# SHDN-S05-V00-Connector.net
KiCad netlist of a schematic drawn in Altium Designer
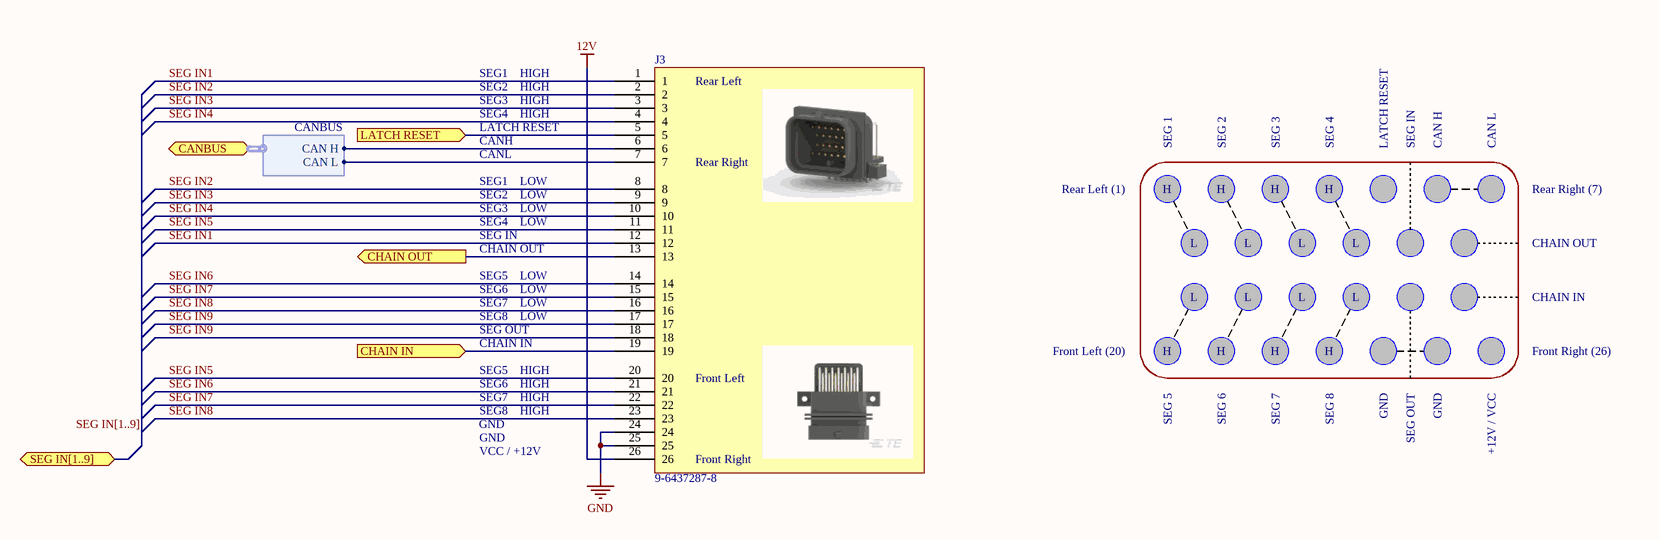
[diagram p0: SHDN-S05-V00-Connector.SchDoc]

(export (version "E")
  (design (tool "Eeschema 10.0.6"))
  (components
    (comp (ref "J3")
      (value "9-6437287-8")
      (footprint "SUPERSEAL RIGHT 26WAY")
      (description "Connector Header Through Hole, Right Angle 26 position 0.118\" (3.00mm)")
      (libsource (lib "QUTMS_SupersealPCB") (part "9-6437287-8"))
    )
  )
  (nets
    (net (code "2") (name "/CAN H") (class "Default")
      (node (ref "J3") (pin "6") (pinfunction "6_6") (pintype "passive"))
    )
    (net (code "3") (name "/CAN L") (class "Default")
      (node (ref "J3") (pin "7") (pinfunction "7_7") (pintype "passive"))
    )
    (net (code "4") (name "/CHAIN IN") (class "Default")
      (node (ref "J3") (pin "19") (pinfunction "19_19") (pintype "passive"))
    )
    (net (code "5") (name "/CHAIN OUT") (class "Default")
      (node (ref "J3") (pin "13") (pinfunction "13_13") (pintype "passive"))
    )
    (net (code "6") (name "/LATCH RESET") (class "Default")
      (node (ref "J3") (pin "5") (pinfunction "5_5") (pintype "passive"))
    )
    (net (code "7") (name "/SEG IN1") (class "Default")
      (node (ref "J3") (pin "1") (pinfunction "1_1") (pintype "passive"))
      (node (ref "J3") (pin "12") (pinfunction "12_12") (pintype "passive"))
    )
    (net (code "8") (name "/SEG IN2") (class "Default")
      (node (ref "J3") (pin "2") (pinfunction "2_2") (pintype "passive"))
      (node (ref "J3") (pin "8") (pinfunction "8_8") (pintype "passive"))
    )
    (net (code "9") (name "/SEG IN3") (class "Default")
      (node (ref "J3") (pin "3") (pinfunction "3_3") (pintype "passive"))
      (node (ref "J3") (pin "9") (pinfunction "9_9") (pintype "passive"))
    )
    (net (code "10") (name "/SEG IN4") (class "Default")
      (node (ref "J3") (pin "10") (pinfunction "10_10") (pintype "passive"))
      (node (ref "J3") (pin "4") (pinfunction "4_4") (pintype "passive"))
    )
    (net (code "11") (name "/SEG IN5") (class "Default")
      (node (ref "J3") (pin "11") (pinfunction "11_11") (pintype "passive"))
      (node (ref "J3") (pin "20") (pinfunction "20_20") (pintype "passive"))
    )
    (net (code "12") (name "/SEG IN6") (class "Default")
      (node (ref "J3") (pin "14") (pinfunction "14_14") (pintype "passive"))
      (node (ref "J3") (pin "21") (pinfunction "21_21") (pintype "passive"))
    )
    (net (code "13") (name "/SEG IN7") (class "Default")
      (node (ref "J3") (pin "15") (pinfunction "15_15") (pintype "passive"))
      (node (ref "J3") (pin "22") (pinfunction "22_22") (pintype "passive"))
    )
    (net (code "14") (name "/SEG IN8") (class "Default")
      (node (ref "J3") (pin "16") (pinfunction "16_16") (pintype "passive"))
      (node (ref "J3") (pin "23") (pinfunction "23_23") (pintype "passive"))
    )
    (net (code "15") (name "/SEG IN9") (class "Default")
      (node (ref "J3") (pin "17") (pinfunction "17_17") (pintype "passive"))
      (node (ref "J3") (pin "18") (pinfunction "18_18") (pintype "passive"))
    )
    (net (code "18") (name "12V") (class "Default")
      (node (ref "J3") (pin "26") (pinfunction "26_26") (pintype "passive"))
    )
    (net (code "19") (name "GND") (class "Default")
      (node (ref "J3") (pin "24") (pinfunction "24_24") (pintype "passive"))
      (node (ref "J3") (pin "25") (pinfunction "25_25") (pintype "passive"))
    )
  )
)
